# INPUT.net
KiCad netlist of a schematic drawn in Altium Designer
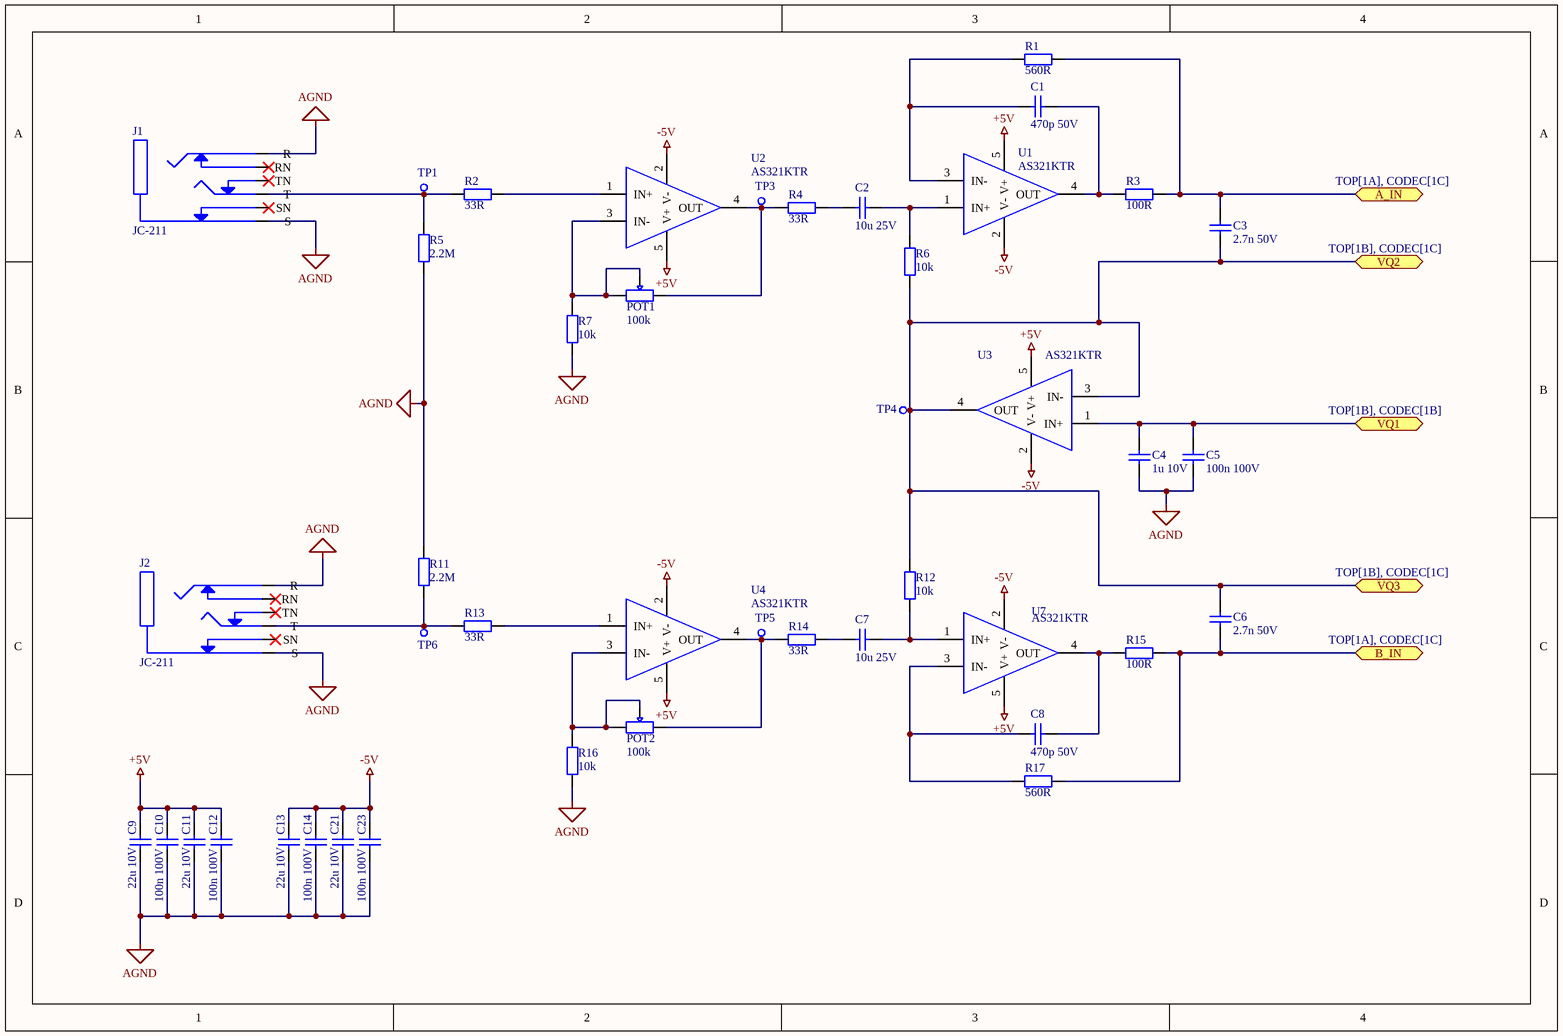
[diagram p0: INPUT.SchDoc]

(export (version "E")
  (design (tool "Eeschema 10.0.6"))
  (components
    (comp (ref "C1")
      (value "470p 50V")
      (footprint "FOOTPRINTS:CAPACITOR 0805")
      (description "Capacitor: ceramic; MLCC; 470pF; 50V; X7R; ±10%; SMD; 0805")
      (fields
        (field (name "MANUFACTURER") "KEMET")
        (field (name "MANUFACTURER PART NUMBER") "C0805C471K5RAC")
      )
      (libsource (lib "SYMBOLS") (part "Capacitor 470p 50V 10% X7R 0805"))
    )
    (comp (ref "C2")
      (value "10u 25V")
      (footprint "FOOTPRINTS:CAPACITOR 0805")
      (description "Capacitor: ceramic; MLCC; 10uF; 25V; X5R; ±10%; SMD; 0805")
      (fields
        (field (name "MANUFACTURER") "MURATA")
        (field (name "MANUFACTURER PART NUMBER") "GRM21BR61E106KA73K")
      )
      (libsource (lib "SYMBOLS") (part "Capacitor 10u 25V 10% X5R 0805"))
    )
    (comp (ref "C3")
      (value "2.7n 50V")
      (footprint "FOOTPRINTS:CAPACITOR 0805")
      (description "Capacitor: ceramic; MLCC; 2.7nF; 50V; X7R; ±10%; SMD; 0805")
      (fields
        (field (name "MANUFACTURER") "KYOCERA AVX")
        (field (name "MANUFACTURER PART NUMBER") "08055C272KAT2A")
      )
      (libsource (lib "SYMBOLS") (part "Capacitor 2.7n 50V ±2% X7R 0805"))
    )
    (comp (ref "C4")
      (value "1u 10V")
      (footprint "FOOTPRINTS:CAPACITOR 0805")
      (description "Capacitor: ceramic; MLCC; 1uF; 10V; X7R; ±10%; SMD; 0805")
      (fields
        (field (name "MANUFACTURER") "YAGEO")
        (field (name "MANUFACTURER PART NUMBER") "CC0805KKX7R6BB105")
      )
      (libsource (lib "SYMBOLS") (part "Capacitor 1u 10V 10% X7R 0805"))
    )
    (comp (ref "C5")
      (value "100n 100V")
      (footprint "FOOTPRINTS:CAPACITOR 0805")
      (description "Capacitor: ceramic; MLCC; 100nF; 100V; X7R; ±10%; SMD; 0805")
      (fields
        (field (name "MANUFACTURER") "YAGEO")
        (field (name "MANUFACTURER PART NUMBER") "CC0805KKX7R0BB104")
      )
      (libsource (lib "SYMBOLS") (part "Capacitor 100n 100V 10% X7R 0805"))
    )
    (comp (ref "C6")
      (value "2.7n 50V")
      (footprint "FOOTPRINTS:CAPACITOR 0805")
      (description "Capacitor: ceramic; MLCC; 2.7nF; 50V; X7R; ±10%; SMD; 0805")
      (fields
        (field (name "MANUFACTURER") "KYOCERA AVX")
        (field (name "MANUFACTURER PART NUMBER") "08055C272KAT2A")
      )
      (libsource (lib "SYMBOLS") (part "Capacitor 2.7n 50V ±2% X7R 0805"))
    )
    (comp (ref "C7")
      (value "10u 25V")
      (footprint "FOOTPRINTS:CAPACITOR 0805")
      (description "Capacitor: ceramic; MLCC; 10uF; 25V; X5R; ±10%; SMD; 0805")
      (fields
        (field (name "MANUFACTURER") "MURATA")
        (field (name "MANUFACTURER PART NUMBER") "GRM21BR61E106KA73K")
      )
      (libsource (lib "SYMBOLS") (part "Capacitor 10u 25V 10% X5R 0805"))
    )
    (comp (ref "C8")
      (value "470p 50V")
      (footprint "FOOTPRINTS:CAPACITOR 0805")
      (description "Capacitor: ceramic; MLCC; 470pF; 50V; X7R; ±10%; SMD; 0805")
      (fields
        (field (name "MANUFACTURER") "KEMET")
        (field (name "MANUFACTURER PART NUMBER") "C0805C471K5RAC")
      )
      (libsource (lib "SYMBOLS") (part "Capacitor 470p 50V 10% X7R 0805"))
    )
    (comp (ref "C9")
      (value "22u 10V")
      (footprint "FOOTPRINTS:CAPACITOR 0805")
      (description "Capacitor: ceramic; 22uF; 10V; X5R; ±20%; SMD; 0805")
      (fields
        (field (name "MANUFACTURER") "SAMSUNG")
        (field (name "MANUFACTURER PART NUMBER") "CL21A226MPQNNNE")
      )
      (libsource (lib "SYMBOLS") (part "Capacitor 22u 10V 20% X5R 0805"))
    )
    (comp (ref "C10")
      (value "100n 100V")
      (footprint "FOOTPRINTS:CAPACITOR 0805")
      (description "Capacitor: ceramic; MLCC; 100nF; 100V; X7R; ±10%; SMD; 0805")
      (fields
        (field (name "MANUFACTURER") "YAGEO")
        (field (name "MANUFACTURER PART NUMBER") "CC0805KKX7R0BB104")
      )
      (libsource (lib "SYMBOLS") (part "Capacitor 100n 100V 10% X7R 0805"))
    )
    (comp (ref "C11")
      (value "22u 10V")
      (footprint "FOOTPRINTS:CAPACITOR 0805")
      (description "Capacitor: ceramic; 22uF; 10V; X5R; ±20%; SMD; 0805")
      (fields
        (field (name "MANUFACTURER") "SAMSUNG")
        (field (name "MANUFACTURER PART NUMBER") "CL21A226MPQNNNE")
      )
      (libsource (lib "SYMBOLS") (part "Capacitor 22u 10V 20% X5R 0805"))
    )
    (comp (ref "C12")
      (value "100n 100V")
      (footprint "FOOTPRINTS:CAPACITOR 0805")
      (description "Capacitor: ceramic; MLCC; 100nF; 100V; X7R; ±10%; SMD; 0805")
      (fields
        (field (name "MANUFACTURER") "YAGEO")
        (field (name "MANUFACTURER PART NUMBER") "CC0805KKX7R0BB104")
      )
      (libsource (lib "SYMBOLS") (part "Capacitor 100n 100V 10% X7R 0805"))
    )
    (comp (ref "C13")
      (value "22u 10V")
      (footprint "FOOTPRINTS:CAPACITOR 0805")
      (description "Capacitor: ceramic; 22uF; 10V; X5R; ±20%; SMD; 0805")
      (fields
        (field (name "MANUFACTURER") "SAMSUNG")
        (field (name "MANUFACTURER PART NUMBER") "CL21A226MPQNNNE")
      )
      (libsource (lib "SYMBOLS") (part "Capacitor 22u 10V 20% X5R 0805"))
    )
    (comp (ref "C14")
      (value "100n 100V")
      (footprint "FOOTPRINTS:CAPACITOR 0805")
      (description "Capacitor: ceramic; MLCC; 100nF; 100V; X7R; ±10%; SMD; 0805")
      (fields
        (field (name "MANUFACTURER") "YAGEO")
        (field (name "MANUFACTURER PART NUMBER") "CC0805KKX7R0BB104")
      )
      (libsource (lib "SYMBOLS") (part "Capacitor 100n 100V 10% X7R 0805"))
    )
    (comp (ref "C21")
      (value "22u 10V")
      (footprint "FOOTPRINTS:CAPACITOR 0805")
      (description "Capacitor: ceramic; 22uF; 10V; X5R; ±20%; SMD; 0805")
      (fields
        (field (name "MANUFACTURER") "SAMSUNG")
        (field (name "MANUFACTURER PART NUMBER") "CL21A226MPQNNNE")
      )
      (libsource (lib "SYMBOLS") (part "Capacitor 22u 10V 20% X5R 0805"))
    )
    (comp (ref "C23")
      (value "100n 100V")
      (footprint "FOOTPRINTS:CAPACITOR 0805")
      (description "Capacitor: ceramic; MLCC; 100nF; 100V; X7R; ±10%; SMD; 0805")
      (fields
        (field (name "MANUFACTURER") "YAGEO")
        (field (name "MANUFACTURER PART NUMBER") "CC0805KKX7R0BB104")
      )
      (libsource (lib "SYMBOLS") (part "Capacitor 100n 100V 10% X7R 0805"))
    )
    (comp (ref "J1")
      (value "JC-211")
      (footprint "FOOTPRINTS:AMPHENOL ACJM-MHDR")
      (description "Socket; Jack 6,3mm; female; mono; ways: 2; for panel mounting; THT")
      (fields (field (name "MANUFACTURER") "NINIGI"))
      (libsource (lib "SYMBOLS") (part "Mechanical Jack 6.3mm Socket PCB THT JC-211"))
    )
    (comp (ref "J2")
      (value "JC-211")
      (footprint "FOOTPRINTS:AMPHENOL ACJM-MHDR")
      (description "Socket; Jack 6,3mm; female; mono; ways: 2; for panel mounting; THT")
      (fields (field (name "MANUFACTURER") "NINIGI"))
      (libsource (lib "SYMBOLS") (part "Mechanical Jack 6.3mm Socket PCB THT JC-211"))
    )
    (comp (ref "POT1")
      (value "100k")
      (footprint "FOOTPRINTS:POTENTIOMETER 3362P")
      (description "Trimmer Resistors - Through Hole 1/4\"SQ 100KOHMS 10% 0.5WATTS")
      (fields
        (field (name "MANUFACTURER") "Bourns")
        (field (name "MANUFACTURER PART NUMBER") "3362P-1-104LF")
      )
      (libsource (lib "SYMBOLS") (part "Potentiometer Trimmer 100k THT 3362P"))
    )
    (comp (ref "POT2")
      (value "100k")
      (footprint "FOOTPRINTS:POTENTIOMETER 3362P")
      (description "Trimmer Resistors - Through Hole 1/4\"SQ 100KOHMS 10% 0.5WATTS")
      (fields
        (field (name "MANUFACTURER") "Bourns")
        (field (name "MANUFACTURER PART NUMBER") "3362P-1-104LF")
      )
      (libsource (lib "SYMBOLS") (part "Potentiometer Trimmer 100k THT 3362P"))
    )
    (comp (ref "R1")
      (value "560R")
      (footprint "FOOTPRINTS:RESISTOR 0805")
      (description "Resistor: thick film; SMD; 0805; 560Ω; 0.125W; ±1%; -55÷155°C")
      (fields
        (field (name "MANUFACTURER") "Yageo")
        (field (name "MANUFACTURER PART NUMBER") "RC0805FR-07560R")
      )
      (libsource (lib "SYMBOLS") (part "Resistor 560R 1% 1/8W 0805"))
    )
    (comp (ref "R2")
      (value "33R")
      (footprint "FOOTPRINTS:RESISTOR 0805")
      (description "Resistor: thick film; SMD; 0805; 33Ω; 0.125W; ±1%; -55÷155°C")
      (fields
        (field (name "MANUFACTURER") "Yageo")
        (field (name "MANUFACTURER PART NUMBER") "RC0805FR-0733R")
      )
      (libsource (lib "SYMBOLS") (part "Resistor 33R 1% 1/8W 0805"))
    )
    (comp (ref "R3")
      (value "100R")
      (footprint "FOOTPRINTS:RESISTOR 0805")
      (description "Resistor: thick film; SMD; 0805; 100Ω; 0.125W; ±1%; -55÷155°C")
      (fields
        (field (name "MANUFACTURER") "Yageo")
        (field (name "MANUFACTURER PART NUMBER") "RC0805FR-07100R")
      )
      (libsource (lib "SYMBOLS") (part "Resistor 100R 1% 1/8W 0805"))
    )
    (comp (ref "R4")
      (value "33R")
      (footprint "FOOTPRINTS:RESISTOR 0805")
      (description "Resistor: thick film; SMD; 0805; 33Ω; 0.125W; ±1%; -55÷155°C")
      (fields
        (field (name "MANUFACTURER") "Yageo")
        (field (name "MANUFACTURER PART NUMBER") "RC0805FR-0733R")
      )
      (libsource (lib "SYMBOLS") (part "Resistor 33R 1% 1/8W 0805"))
    )
    (comp (ref "R5")
      (value "2.2M")
      (footprint "FOOTPRINTS:RESISTOR 0805")
      (description "Resistor: thick film; SMD; 0805; 2.2MΩ; 0.125W; ±5%; -55÷155°C")
      (fields
        (field (name "MANUFACTURER") "Yageo")
        (field (name "MANUFACTURER PART NUMBER") "RC0805JR-072M2")
      )
      (libsource (lib "SYMBOLS") (part "Resistor 2.2M 5% 1/8W 0805"))
    )
    (comp (ref "R6")
      (value "10k")
      (footprint "FOOTPRINTS:RESISTOR 0805")
      (description "Resistor: thick film; SMD; 0805; 10kΩ; 0.125W; ±1%; -55÷155°C")
      (fields
        (field (name "MANUFACTURER") "Yageo")
        (field (name "MANUFACTURER PART NUMBER") "RC0805FR-0710K")
      )
      (libsource (lib "SYMBOLS") (part "Resistor 10k 1% 1/8W 0805"))
    )
    (comp (ref "R7")
      (value "10k")
      (footprint "FOOTPRINTS:RESISTOR 0805")
      (description "Resistor: thick film; SMD; 0805; 10kΩ; 0.125W; ±1%; -55÷155°C")
      (fields
        (field (name "MANUFACTURER") "Yageo")
        (field (name "MANUFACTURER PART NUMBER") "RC0805FR-0710K")
      )
      (libsource (lib "SYMBOLS") (part "Resistor 10k 1% 1/8W 0805"))
    )
    (comp (ref "R11")
      (value "2.2M")
      (footprint "FOOTPRINTS:RESISTOR 0805")
      (description "Resistor: thick film; SMD; 0805; 2.2MΩ; 0.125W; ±5%; -55÷155°C")
      (fields
        (field (name "MANUFACTURER") "Yageo")
        (field (name "MANUFACTURER PART NUMBER") "RC0805JR-072M2")
      )
      (libsource (lib "SYMBOLS") (part "Resistor 2.2M 5% 1/8W 0805"))
    )
    (comp (ref "R12")
      (value "10k")
      (footprint "FOOTPRINTS:RESISTOR 0805")
      (description "Resistor: thick film; SMD; 0805; 10kΩ; 0.125W; ±1%; -55÷155°C")
      (fields
        (field (name "MANUFACTURER") "Yageo")
        (field (name "MANUFACTURER PART NUMBER") "RC0805FR-0710K")
      )
      (libsource (lib "") (part "Resistor 10k 1% 1/8W 0805_1"))
    )
    (comp (ref "R13")
      (value "33R")
      (footprint "FOOTPRINTS:RESISTOR 0805")
      (description "Resistor: thick film; SMD; 0805; 33Ω; 0.125W; ±1%; -55÷155°C")
      (fields
        (field (name "MANUFACTURER") "Yageo")
        (field (name "MANUFACTURER PART NUMBER") "RC0805FR-0733R")
      )
      (libsource (lib "SYMBOLS") (part "Resistor 33R 1% 1/8W 0805"))
    )
    (comp (ref "R14")
      (value "33R")
      (footprint "FOOTPRINTS:RESISTOR 0805")
      (description "Resistor: thick film; SMD; 0805; 33Ω; 0.125W; ±1%; -55÷155°C")
      (fields
        (field (name "MANUFACTURER") "Yageo")
        (field (name "MANUFACTURER PART NUMBER") "RC0805FR-0733R")
      )
      (libsource (lib "SYMBOLS") (part "Resistor 33R 1% 1/8W 0805"))
    )
    (comp (ref "R15")
      (value "100R")
      (footprint "FOOTPRINTS:RESISTOR 0805")
      (description "Resistor: thick film; SMD; 0805; 100Ω; 0.125W; ±1%; -55÷155°C")
      (fields
        (field (name "MANUFACTURER") "Yageo")
        (field (name "MANUFACTURER PART NUMBER") "RC0805FR-07100R")
      )
      (libsource (lib "") (part "Resistor 100R 1% 1/8W 0805_1"))
    )
    (comp (ref "R16")
      (value "10k")
      (footprint "FOOTPRINTS:RESISTOR 0805")
      (description "Resistor: thick film; SMD; 0805; 10kΩ; 0.125W; ±1%; -55÷155°C")
      (fields
        (field (name "MANUFACTURER") "Yageo")
        (field (name "MANUFACTURER PART NUMBER") "RC0805FR-0710K")
      )
      (libsource (lib "SYMBOLS") (part "Resistor 10k 1% 1/8W 0805"))
    )
    (comp (ref "R17")
      (value "560R")
      (footprint "FOOTPRINTS:RESISTOR 0805")
      (description "Resistor: thick film; SMD; 0805; 560Ω; 0.125W; ±1%; -55÷155°C")
      (fields
        (field (name "MANUFACTURER") "Yageo")
        (field (name "MANUFACTURER PART NUMBER") "RC0805FR-07560R")
      )
      (libsource (lib "") (part "Resistor 560R 1% 1/8W 0805_1"))
    )
    (comp (ref "TP1")
      (value "1mm")
      (footprint "FOOTPRINTS:TEST POINT 1MM")
      (description "Tesp Point 1mm")
      (libsource (lib "SYMBOLS") (part "Mechanical Test Point 1mm"))
    )
    (comp (ref "TP3")
      (value "1mm")
      (footprint "FOOTPRINTS:TEST POINT 1MM")
      (description "Tesp Point 1mm")
      (libsource (lib "SYMBOLS") (part "Mechanical Test Point 1mm"))
    )
    (comp (ref "TP4")
      (value "1mm")
      (footprint "FOOTPRINTS:TEST POINT 1MM")
      (description "Tesp Point 1mm")
      (libsource (lib "SYMBOLS") (part "Mechanical Test Point 1mm"))
    )
    (comp (ref "TP5")
      (value "1mm")
      (footprint "FOOTPRINTS:TEST POINT 1MM")
      (description "Tesp Point 1mm")
      (libsource (lib "SYMBOLS") (part "Mechanical Test Point 1mm"))
    )
    (comp (ref "TP6")
      (value "1mm")
      (footprint "FOOTPRINTS:TEST POINT 1MM")
      (description "Tesp Point 1mm")
      (libsource (lib "SYMBOLS") (part "Mechanical Test Point 1mm"))
    )
    (comp (ref "U1")
      (value "AS321KTR")
      (footprint "FOOTPRINTS:SOT23-5")
      (description "IC: operational amplifier; 3÷36V; Ch: 1; SOT23-5; reel,tape")
      (fields
        (field (name "MANUFACTURER") "DIODES INCORPORATED")
        (field (name "MANUFACTURER PART NUMBER") "AS321KTR-G1")
      )
      (libsource (lib "SYMBOLS") (part "IC Op-Amp Single AS321KTR SOT23-5"))
    )
    (comp (ref "U2")
      (value "AS321KTR")
      (footprint "FOOTPRINTS:SOT23-5")
      (description "IC: operational amplifier; 3÷36V; Ch: 1; SOT23-5; reel,tape")
      (fields
        (field (name "MANUFACTURER") "DIODES INCORPORATED")
        (field (name "MANUFACTURER PART NUMBER") "AS321KTR-G1")
      )
      (libsource (lib "SYMBOLS") (part "IC Op-Amp Single AS321KTR SOT23-5"))
    )
    (comp (ref "U3")
      (value "AS321KTR")
      (footprint "FOOTPRINTS:SOT23-5")
      (description "IC: operational amplifier; 3÷36V; Ch: 1; SOT23-5; reel,tape")
      (fields
        (field (name "MANUFACTURER") "DIODES INCORPORATED")
        (field (name "MANUFACTURER PART NUMBER") "AS321KTR-G1")
      )
      (libsource (lib "SYMBOLS") (part "IC Op-Amp Single AS321KTR SOT23-5"))
    )
    (comp (ref "U4")
      (value "AS321KTR")
      (footprint "FOOTPRINTS:SOT23-5")
      (description "IC: operational amplifier; 3÷36V; Ch: 1; SOT23-5; reel,tape")
      (fields
        (field (name "MANUFACTURER") "DIODES INCORPORATED")
        (field (name "MANUFACTURER PART NUMBER") "AS321KTR-G1")
      )
      (libsource (lib "SYMBOLS") (part "IC Op-Amp Single AS321KTR SOT23-5"))
    )
    (comp (ref "U7")
      (value "AS321KTR")
      (footprint "FOOTPRINTS:SOT23-5")
      (description "IC: operational amplifier; 3÷36V; Ch: 1; SOT23-5; reel,tape")
      (fields
        (field (name "MANUFACTURER") "DIODES INCORPORATED")
        (field (name "MANUFACTURER PART NUMBER") "AS321KTR-G1")
      )
      (libsource (lib "SYMBOLS") (part "IC Op-Amp Single AS321KTR SOT23-5"))
    )
  )
  (nets
    (net (code "1") (name "+5V") (class "Default")
      (node (ref "C10") (pin "2") (pinfunction "2_2") (pintype "passive"))
      (node (ref "C11") (pin "2") (pinfunction "2_2") (pintype "passive"))
      (node (ref "C12") (pin "2") (pinfunction "2_2") (pintype "passive"))
      (node (ref "C9") (pin "2") (pinfunction "2_2") (pintype "passive"))
      (node (ref "U1") (pin "5") (pinfunction "V+_5") (pintype "passive"))
      (node (ref "U2") (pin "5") (pinfunction "V+_5") (pintype "passive"))
      (node (ref "U3") (pin "5") (pinfunction "V+_5") (pintype "passive"))
      (node (ref "U4") (pin "5") (pinfunction "V+_5") (pintype "passive"))
      (node (ref "U7") (pin "5") (pinfunction "V+_5") (pintype "passive"))
    )
    (net (code "2") (name "-5V") (class "Default")
      (node (ref "C13") (pin "2") (pinfunction "2_2") (pintype "passive"))
      (node (ref "C14") (pin "2") (pinfunction "2_2") (pintype "passive"))
      (node (ref "C21") (pin "2") (pinfunction "2_2") (pintype "passive"))
      (node (ref "C23") (pin "2") (pinfunction "2_2") (pintype "passive"))
      (node (ref "U1") (pin "2") (pinfunction "V-_2") (pintype "passive"))
      (node (ref "U2") (pin "2") (pinfunction "V-_2") (pintype "passive"))
      (node (ref "U3") (pin "2") (pinfunction "V-_2") (pintype "passive"))
      (node (ref "U4") (pin "2") (pinfunction "V-_2") (pintype "passive"))
      (node (ref "U7") (pin "2") (pinfunction "V-_2") (pintype "passive"))
    )
    (net (code "3") (name "/A_IN") (class "Default")
      (node (ref "C3") (pin "2") (pinfunction "2_2") (pintype "passive"))
      (node (ref "R1") (pin "2") (pinfunction "2_2") (pintype "passive"))
      (node (ref "R3") (pin "2") (pinfunction "2_2") (pintype "passive"))
    )
    (net (code "4") (name "/B_IN") (class "Default")
      (node (ref "C6") (pin "2") (pinfunction "2_2") (pintype "passive"))
      (node (ref "R15") (pin "2") (pinfunction "2_2") (pintype "passive"))
      (node (ref "R17") (pin "2") (pinfunction "2_2") (pintype "passive"))
    )
    (net (code "5") (name "/VQ1") (class "Default")
      (node (ref "C4") (pin "2") (pinfunction "2_2") (pintype "passive"))
      (node (ref "C5") (pin "2") (pinfunction "2_2") (pintype "passive"))
      (node (ref "U3") (pin "1") (pinfunction "IN+_1") (pintype "passive"))
    )
    (net (code "6") (name "/VQ2") (class "Default")
      (node (ref "C3") (pin "1") (pinfunction "1_1") (pintype "passive"))
      (node (ref "C6") (pin "1") (pinfunction "1_1") (pintype "passive"))
      (node (ref "R12") (pin "1") (pinfunction "1_1") (pintype "passive"))
      (node (ref "R6") (pin "1") (pinfunction "1_1") (pintype "passive"))
      (node (ref "TP4") (pin "1") (pinfunction "1_1") (pintype "passive"))
      (node (ref "U3") (pin "3") (pinfunction "IN-_3") (pintype "passive"))
      (node (ref "U3") (pin "4") (pinfunction "OUT_4") (pintype "passive"))
    )
    (net (code "7") (name "AGND") (class "Default")
      (node (ref "C10") (pin "1") (pinfunction "1_1") (pintype "passive"))
      (node (ref "C11") (pin "1") (pinfunction "1_1") (pintype "passive"))
      (node (ref "C12") (pin "1") (pinfunction "1_1") (pintype "passive"))
      (node (ref "C13") (pin "1") (pinfunction "1_1") (pintype "passive"))
      (node (ref "C14") (pin "1") (pinfunction "1_1") (pintype "passive"))
      (node (ref "C21") (pin "1") (pinfunction "1_1") (pintype "passive"))
      (node (ref "C23") (pin "1") (pinfunction "1_1") (pintype "passive"))
      (node (ref "C4") (pin "1") (pinfunction "1_1") (pintype "passive"))
      (node (ref "C5") (pin "1") (pinfunction "1_1") (pintype "passive"))
      (node (ref "C9") (pin "1") (pinfunction "1_1") (pintype "passive"))
      (node (ref "J1") (pin "1") (pinfunction "S_1") (pintype "passive"))
      (node (ref "J1") (pin "2") (pinfunction "R_2") (pintype "passive"))
      (node (ref "J2") (pin "1") (pinfunction "S_1") (pintype "passive"))
      (node (ref "J2") (pin "2") (pinfunction "R_2") (pintype "passive"))
      (node (ref "R11") (pin "2") (pinfunction "2_2") (pintype "passive"))
      (node (ref "R16") (pin "1") (pinfunction "1_1") (pintype "passive"))
      (node (ref "R5") (pin "1") (pinfunction "1_1") (pintype "passive"))
      (node (ref "R7") (pin "1") (pinfunction "1_1") (pintype "passive"))
    )
    (net (code "8") (name "Net-(C2-Pad1)") (class "Default")
      (node (ref "C2") (pin "1") (pinfunction "1_1") (pintype "passive"))
      (node (ref "R4") (pin "2") (pinfunction "2_2") (pintype "passive"))
    )
    (net (code "9") (name "Net-(C7-Pad1)") (class "Default")
      (node (ref "C7") (pin "1") (pinfunction "1_1") (pintype "passive"))
      (node (ref "R14") (pin "2") (pinfunction "2_2") (pintype "passive"))
    )
    (net (code "10") (name "Net-(J1-T)") (class "Default")
      (node (ref "J1") (pin "3") (pinfunction "T_3") (pintype "passive"))
      (node (ref "R2") (pin "1") (pinfunction "1_1") (pintype "passive"))
      (node (ref "R5") (pin "2") (pinfunction "2_2") (pintype "passive"))
      (node (ref "TP1") (pin "1") (pinfunction "1_1") (pintype "passive"))
    )
    (net (code "11") (name "Net-(J2-T)") (class "Default")
      (node (ref "J2") (pin "3") (pinfunction "T_3") (pintype "passive"))
      (node (ref "R11") (pin "1") (pinfunction "1_1") (pintype "passive"))
      (node (ref "R13") (pin "1") (pinfunction "1_1") (pintype "passive"))
      (node (ref "TP6") (pin "1") (pinfunction "1_1") (pintype "passive"))
    )
    (net (code "12") (name "Net-(U1-IN+)") (class "Default")
      (node (ref "C2") (pin "2") (pinfunction "2_2") (pintype "passive"))
      (node (ref "R6") (pin "2") (pinfunction "2_2") (pintype "passive"))
      (node (ref "U1") (pin "1") (pinfunction "IN+_1") (pintype "passive"))
    )
    (net (code "13") (name "Net-(U1-IN-)") (class "Default")
      (node (ref "C1") (pin "1") (pinfunction "1_1") (pintype "passive"))
      (node (ref "R1") (pin "1") (pinfunction "1_1") (pintype "passive"))
      (node (ref "U1") (pin "3") (pinfunction "IN-_3") (pintype "passive"))
    )
    (net (code "14") (name "Net-(U1-OUT)") (class "Default")
      (node (ref "C1") (pin "2") (pinfunction "2_2") (pintype "passive"))
      (node (ref "R3") (pin "1") (pinfunction "1_1") (pintype "passive"))
      (node (ref "U1") (pin "4") (pinfunction "OUT_4") (pintype "passive"))
    )
    (net (code "15") (name "Net-(U2-IN+)") (class "Default")
      (node (ref "R2") (pin "2") (pinfunction "2_2") (pintype "passive"))
      (node (ref "U2") (pin "1") (pinfunction "IN+_1") (pintype "passive"))
    )
    (net (code "16") (name "Net-(U2-IN-)") (class "Default")
      (node (ref "POT1") (pin "1") (pinfunction "1_1") (pintype "passive"))
      (node (ref "POT1") (pin "2") (pinfunction "2_2") (pintype "passive"))
      (node (ref "R7") (pin "2") (pinfunction "2_2") (pintype "passive"))
      (node (ref "U2") (pin "3") (pinfunction "IN-_3") (pintype "passive"))
    )
    (net (code "17") (name "Net-(U2-OUT)") (class "Default")
      (node (ref "POT1") (pin "3") (pinfunction "3_3") (pintype "passive"))
      (node (ref "R4") (pin "1") (pinfunction "1_1") (pintype "passive"))
      (node (ref "TP3") (pin "1") (pinfunction "1_1") (pintype "passive"))
      (node (ref "U2") (pin "4") (pinfunction "OUT_4") (pintype "passive"))
    )
    (net (code "18") (name "Net-(U4-IN+)") (class "Default")
      (node (ref "R13") (pin "2") (pinfunction "2_2") (pintype "passive"))
      (node (ref "U4") (pin "1") (pinfunction "IN+_1") (pintype "passive"))
    )
    (net (code "19") (name "Net-(U4-IN-)") (class "Default")
      (node (ref "POT2") (pin "1") (pinfunction "1_1") (pintype "passive"))
      (node (ref "POT2") (pin "2") (pinfunction "2_2") (pintype "passive"))
      (node (ref "R16") (pin "2") (pinfunction "2_2") (pintype "passive"))
      (node (ref "U4") (pin "3") (pinfunction "IN-_3") (pintype "passive"))
    )
    (net (code "20") (name "Net-(U4-OUT)") (class "Default")
      (node (ref "POT2") (pin "3") (pinfunction "3_3") (pintype "passive"))
      (node (ref "R14") (pin "1") (pinfunction "1_1") (pintype "passive"))
      (node (ref "TP5") (pin "1") (pinfunction "1_1") (pintype "passive"))
      (node (ref "U4") (pin "4") (pinfunction "OUT_4") (pintype "passive"))
    )
    (net (code "21") (name "Net-(U7-IN+)") (class "Default")
      (node (ref "C7") (pin "2") (pinfunction "2_2") (pintype "passive"))
      (node (ref "R12") (pin "2") (pinfunction "2_2") (pintype "passive"))
      (node (ref "U7") (pin "1") (pinfunction "IN+_1") (pintype "passive"))
    )
    (net (code "22") (name "Net-(U7-IN-)") (class "Default")
      (node (ref "C8") (pin "1") (pinfunction "1_1") (pintype "passive"))
      (node (ref "R17") (pin "1") (pinfunction "1_1") (pintype "passive"))
      (node (ref "U7") (pin "3") (pinfunction "IN-_3") (pintype "passive"))
    )
    (net (code "23") (name "Net-(U7-OUT)") (class "Default")
      (node (ref "C8") (pin "2") (pinfunction "2_2") (pintype "passive"))
      (node (ref "R15") (pin "1") (pinfunction "1_1") (pintype "passive"))
      (node (ref "U7") (pin "4") (pinfunction "OUT_4") (pintype "passive"))
    )
    (net (code "24") (name "unconnected-(J1-RN-Pad5)") (class "Default")
      (node (ref "J1") (pin "5") (pinfunction "RN_5") (pintype "passive+no_connect"))
    )
    (net (code "25") (name "unconnected-(J1-SN-Pad6)") (class "Default")
      (node (ref "J1") (pin "6") (pinfunction "SN_6") (pintype "passive+no_connect"))
    )
    (net (code "26") (name "unconnected-(J1-TN-Pad4)") (class "Default")
      (node (ref "J1") (pin "4") (pinfunction "TN_4") (pintype "passive+no_connect"))
    )
    (net (code "27") (name "unconnected-(J2-RN-Pad5)") (class "Default")
      (node (ref "J2") (pin "5") (pinfunction "RN_5") (pintype "passive+no_connect"))
    )
    (net (code "28") (name "unconnected-(J2-SN-Pad6)") (class "Default")
      (node (ref "J2") (pin "6") (pinfunction "SN_6") (pintype "passive+no_connect"))
    )
    (net (code "29") (name "unconnected-(J2-TN-Pad4)") (class "Default")
      (node (ref "J2") (pin "4") (pinfunction "TN_4") (pintype "passive+no_connect"))
    )
  )
)
